# yamaHACK.net
KiCad netlist of a schematic drawn in EAGLE
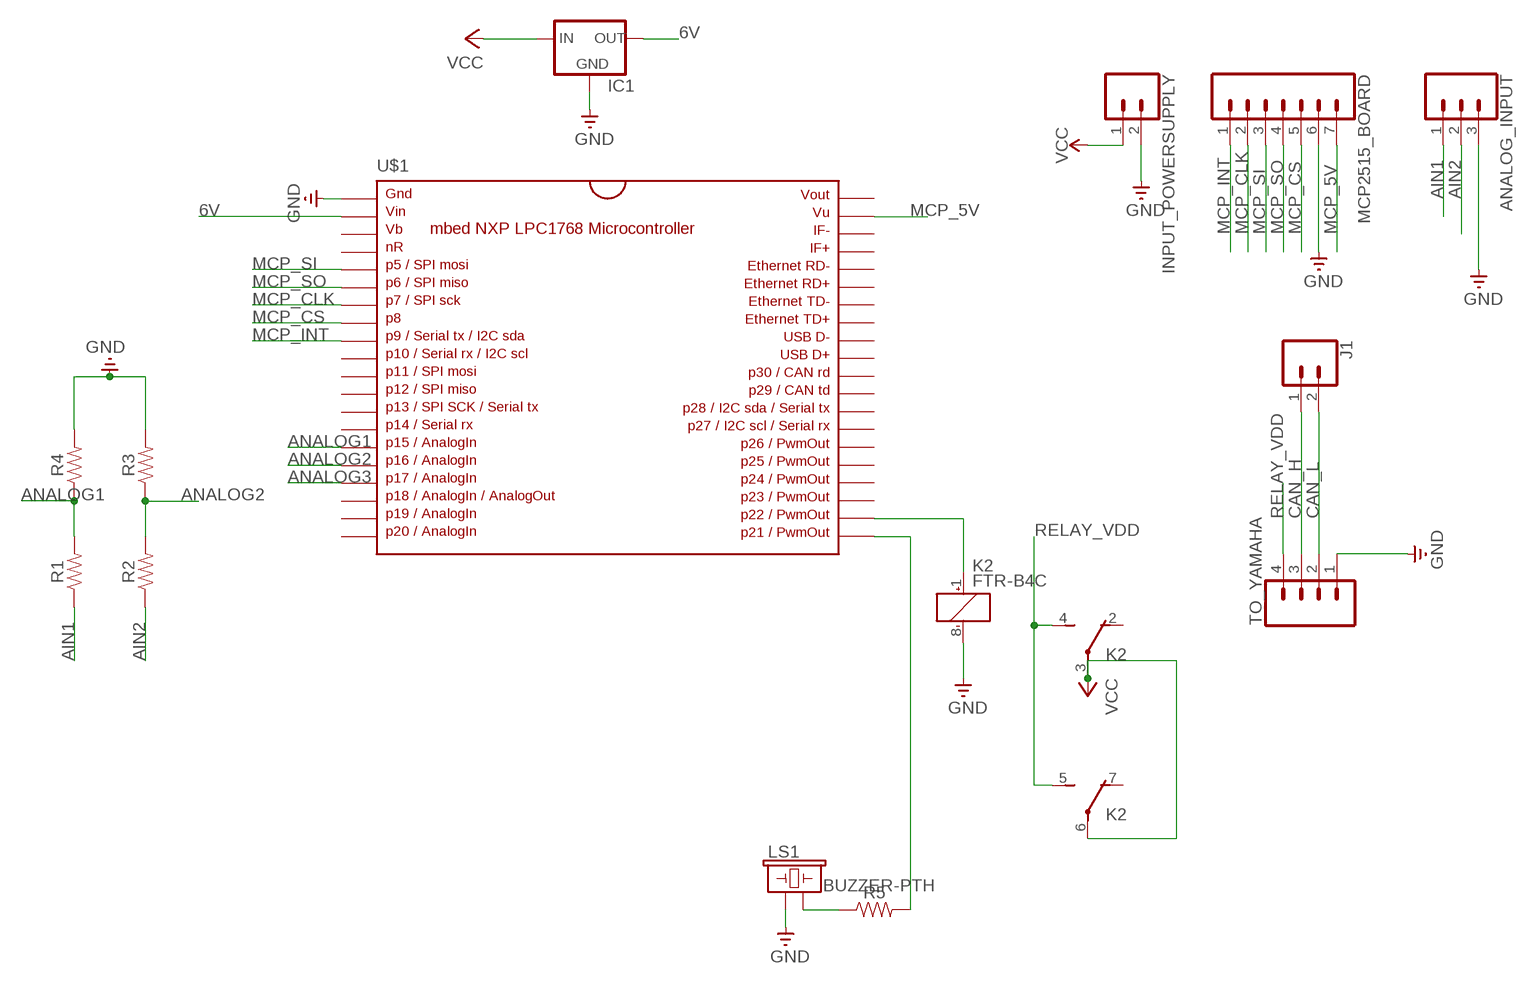
[diagram p0: schematic, sheet 1]

(export (version "E")
  (design (tool "Eeschema 10.0.6"))
  (components
    (comp (ref "ANALOG_INPUT")
      (value "CONN_03LONGPADS")
      (footprint "eagle-import:1X03_LONGPADS")
      (libsource (lib "eagle-import") (part "CONN_03LONGPADS"))
    )
    (comp (ref "IC1")
      (value "78MXXS")
      (footprint "eagle-import:78MXXS")
      (libsource (lib "eagle-import") (part "78MXXS"))
    )
    (comp (ref "INPUT_POWERSUPPLY")
      (value "CONN_02PTH3")
      (footprint "eagle-import:1X02_LONGPADS")
      (libsource (lib "eagle-import") (part "CONN_02PTH3"))
    )
    (comp (ref "J1")
      (value "CONN_02")
      (footprint "eagle-import:1X02")
      (libsource (lib "eagle-import") (part "CONN_02"))
    )
    (comp (ref "K2")
      (value "FTR-B4C")
      (footprint "eagle-import:FTR-B4C")
      (libsource (lib "eagle-import") (part "FTR-B4C"))
    )
    (comp (ref "LS1")
      (value "BUZZER-PTH")
      (footprint "eagle-import:BUZZER-12MM")
      (libsource (lib "eagle-import") (part "BUZZER-PTH"))
    )
    (comp (ref "MCP2515_BOARD")
      (value "CONN_07LONGPADS")
      (footprint "eagle-import:1X07_LONGPADS")
      (libsource (lib "eagle-import") (part "CONN_07LONGPADS"))
    )
    (comp (ref "R1")
      (value "RESISTORAXIAL-0.3")
      (footprint "eagle-import:AXIAL-0.3")
      (libsource (lib "eagle-import") (part "RESISTORAXIAL-0.3"))
    )
    (comp (ref "R2")
      (value "RESISTORAXIAL-0.3")
      (footprint "eagle-import:AXIAL-0.3")
      (libsource (lib "eagle-import") (part "RESISTORAXIAL-0.3"))
    )
    (comp (ref "R3")
      (value "RESISTORAXIAL-0.3")
      (footprint "eagle-import:AXIAL-0.3")
      (libsource (lib "eagle-import") (part "RESISTORAXIAL-0.3"))
    )
    (comp (ref "R4")
      (value "RESISTORAXIAL-0.3")
      (footprint "eagle-import:AXIAL-0.3")
      (libsource (lib "eagle-import") (part "RESISTORAXIAL-0.3"))
    )
    (comp (ref "R5")
      (value "RESISTORAXIAL-0.3")
      (footprint "eagle-import:AXIAL-0.3")
      (libsource (lib "eagle-import") (part "RESISTORAXIAL-0.3"))
    )
    (comp (ref "TO_YAMAHA")
      (value "CONN_04")
      (footprint "eagle-import:1X04")
      (libsource (lib "eagle-import") (part "CONN_04"))
    )
    (comp (ref "U$1")
      (value "MBED1768")
      (footprint "eagle-import:DIL40_0.9")
      (libsource (lib "eagle-import") (part "MBED_NXP_LPC1768"))
    )
  )
  (nets
    (net (code "1") (name "/6V") (class "Default")
      (node (ref "IC1") (pin "OUT") (pinfunction "OUT_OUT") (pintype "passive"))
      (node (ref "U$1") (pin "2") (pinfunction "P$2_2") (pintype "bidirectional"))
    )
    (net (code "2") (name "/AIN1") (class "Default")
      (node (ref "ANALOG_INPUT") (pin "1") (pinfunction "1_1") (pintype "passive"))
      (node (ref "R1") (pin "P$1") (pinfunction "1_P$1") (pintype "passive"))
    )
    (net (code "3") (name "/AIN2") (class "Default")
      (node (ref "ANALOG_INPUT") (pin "2") (pinfunction "2_2") (pintype "passive"))
      (node (ref "R2") (pin "P$1") (pinfunction "1_P$1") (pintype "passive"))
    )
    (net (code "4") (name "/ANALOG1") (class "Default")
      (node (ref "R1") (pin "P$2") (pinfunction "2_P$2") (pintype "passive"))
      (node (ref "R4") (pin "P$1") (pinfunction "1_P$1") (pintype "passive"))
      (node (ref "U$1") (pin "15") (pinfunction "P$15_15") (pintype "bidirectional"))
    )
    (net (code "5") (name "/ANALOG2") (class "Default")
      (node (ref "R2") (pin "P$2") (pinfunction "2_P$2") (pintype "passive"))
      (node (ref "R3") (pin "P$1") (pinfunction "1_P$1") (pintype "passive"))
      (node (ref "U$1") (pin "16") (pinfunction "P$16_16") (pintype "bidirectional"))
    )
    (net (code "6") (name "/ANALOG3") (class "Default")
      (node (ref "U$1") (pin "17") (pinfunction "P$17_17") (pintype "bidirectional"))
    )
    (net (code "7") (name "/CAN_H") (class "Default")
      (node (ref "J1") (pin "1") (pinfunction "1_1") (pintype "passive"))
      (node (ref "TO_YAMAHA") (pin "3") (pinfunction "3_3") (pintype "passive"))
    )
    (net (code "8") (name "/CAN_L") (class "Default")
      (node (ref "J1") (pin "2") (pinfunction "2_2") (pintype "passive"))
      (node (ref "TO_YAMAHA") (pin "2") (pinfunction "2_2") (pintype "passive"))
    )
    (net (code "9") (name "/MCP_5V") (class "Default")
      (node (ref "MCP2515_BOARD") (pin "7") (pinfunction "7_7") (pintype "passive"))
      (node (ref "U$1") (pin "39") (pinfunction "P$39_39") (pintype "bidirectional"))
    )
    (net (code "10") (name "/MCP_CLK") (class "Default")
      (node (ref "MCP2515_BOARD") (pin "2") (pinfunction "2_2") (pintype "passive"))
      (node (ref "U$1") (pin "7") (pinfunction "P$7_7") (pintype "bidirectional"))
    )
    (net (code "11") (name "/MCP_CS") (class "Default")
      (node (ref "MCP2515_BOARD") (pin "5") (pinfunction "5_5") (pintype "passive"))
      (node (ref "U$1") (pin "8") (pinfunction "P$8_8") (pintype "bidirectional"))
    )
    (net (code "12") (name "/MCP_INT") (class "Default")
      (node (ref "MCP2515_BOARD") (pin "1") (pinfunction "1_1") (pintype "passive"))
      (node (ref "U$1") (pin "9") (pinfunction "P$9_9") (pintype "bidirectional"))
    )
    (net (code "13") (name "/MCP_SI") (class "Default")
      (node (ref "MCP2515_BOARD") (pin "3") (pinfunction "3_3") (pintype "passive"))
      (node (ref "U$1") (pin "5") (pinfunction "P$5_5") (pintype "bidirectional"))
    )
    (net (code "14") (name "/MCP_SO") (class "Default")
      (node (ref "MCP2515_BOARD") (pin "4") (pinfunction "4_4") (pintype "passive"))
      (node (ref "U$1") (pin "6") (pinfunction "P$6_6") (pintype "bidirectional"))
    )
    (net (code "15") (name "/RELAY_VDD") (class "Default")
      (node (ref "K2") (pin "4") (pinfunction "S_4") (pintype "passive"))
      (node (ref "K2") (pin "5") (pinfunction "S_5") (pintype "passive"))
      (node (ref "TO_YAMAHA") (pin "4") (pinfunction "4_4") (pintype "passive"))
    )
    (net (code "16") (name "GND") (class "Default")
      (node (ref "ANALOG_INPUT") (pin "3") (pinfunction "3_3") (pintype "passive"))
      (node (ref "IC1") (pin "GND") (pinfunction "GND_GND") (pintype "input"))
      (node (ref "INPUT_POWERSUPPLY") (pin "2") (pinfunction "2_2") (pintype "passive"))
      (node (ref "K2") (pin "8") (pinfunction "-_8") (pintype "passive"))
      (node (ref "LS1") (pin "+") (pinfunction "1_+") (pintype "passive"))
      (node (ref "MCP2515_BOARD") (pin "6") (pinfunction "6_6") (pintype "passive"))
      (node (ref "R3") (pin "P$2") (pinfunction "2_P$2") (pintype "passive"))
      (node (ref "R4") (pin "P$2") (pinfunction "2_P$2") (pintype "passive"))
      (node (ref "TO_YAMAHA") (pin "1") (pinfunction "1_1") (pintype "passive"))
      (node (ref "U$1") (pin "1") (pinfunction "P$1_1") (pintype "bidirectional"))
    )
    (net (code "17") (name "Net-(K2C-+)") (class "Default")
      (node (ref "K2") (pin "1") (pinfunction "+_1") (pintype "passive"))
      (node (ref "U$1") (pin "22") (pinfunction "P$22_22") (pintype "bidirectional"))
    )
    (net (code "18") (name "Net-(LS1-2)") (class "Default")
      (node (ref "LS1") (pin "-") (pinfunction "2_-") (pintype "passive"))
      (node (ref "R5") (pin "P$1") (pinfunction "1_P$1") (pintype "passive"))
    )
    (net (code "19") (name "Net-(R5-2)") (class "Default")
      (node (ref "R5") (pin "P$2") (pinfunction "2_P$2") (pintype "passive"))
      (node (ref "U$1") (pin "21") (pinfunction "P$21_21") (pintype "bidirectional"))
    )
    (net (code "20") (name "VCC") (class "Default")
      (node (ref "IC1") (pin "IN") (pinfunction "IN_IN") (pintype "input"))
      (node (ref "INPUT_POWERSUPPLY") (pin "1") (pinfunction "1_1") (pintype "passive"))
      (node (ref "K2") (pin "3") (pinfunction "P_3") (pintype "passive"))
      (node (ref "K2") (pin "6") (pinfunction "P_6") (pintype "passive"))
    )
    (net (code "21") (name "unconnected-(K2A-O-Pad2)") (class "Default")
      (node (ref "K2") (pin "2") (pinfunction "O_2") (pintype "passive"))
    )
    (net (code "22") (name "unconnected-(K2B-O-Pad7)") (class "Default")
      (node (ref "K2") (pin "7") (pinfunction "O_7") (pintype "passive"))
    )
    (net (code "23") (name "unconnected-(U$1-P$3-Pad3)") (class "Default")
      (node (ref "U$1") (pin "3") (pinfunction "P$3_3") (pintype "bidirectional"))
    )
    (net (code "24") (name "unconnected-(U$1-P$4-Pad4)") (class "Default")
      (node (ref "U$1") (pin "4") (pinfunction "P$4_4") (pintype "bidirectional"))
    )
    (net (code "25") (name "unconnected-(U$1-P$10-Pad10)") (class "Default")
      (node (ref "U$1") (pin "10") (pinfunction "P$10_10") (pintype "bidirectional"))
    )
    (net (code "26") (name "unconnected-(U$1-P$11-Pad11)") (class "Default")
      (node (ref "U$1") (pin "11") (pinfunction "P$11_11") (pintype "bidirectional"))
    )
    (net (code "27") (name "unconnected-(U$1-P$12-Pad12)") (class "Default")
      (node (ref "U$1") (pin "12") (pinfunction "P$12_12") (pintype "bidirectional"))
    )
    (net (code "28") (name "unconnected-(U$1-P$13-Pad13)") (class "Default")
      (node (ref "U$1") (pin "13") (pinfunction "P$13_13") (pintype "bidirectional"))
    )
    (net (code "29") (name "unconnected-(U$1-P$14-Pad14)") (class "Default")
      (node (ref "U$1") (pin "14") (pinfunction "P$14_14") (pintype "bidirectional"))
    )
    (net (code "30") (name "unconnected-(U$1-P$18-Pad18)") (class "Default")
      (node (ref "U$1") (pin "18") (pinfunction "P$18_18") (pintype "bidirectional"))
    )
    (net (code "31") (name "unconnected-(U$1-P$19-Pad19)") (class "Default")
      (node (ref "U$1") (pin "19") (pinfunction "P$19_19") (pintype "bidirectional"))
    )
    (net (code "32") (name "unconnected-(U$1-P$20-Pad20)") (class "Default")
      (node (ref "U$1") (pin "20") (pinfunction "P$20_20") (pintype "bidirectional"))
    )
    (net (code "33") (name "unconnected-(U$1-P$23-Pad23)") (class "Default")
      (node (ref "U$1") (pin "23") (pinfunction "P$23_23") (pintype "bidirectional"))
    )
    (net (code "34") (name "unconnected-(U$1-P$24-Pad24)") (class "Default")
      (node (ref "U$1") (pin "24") (pinfunction "P$24_24") (pintype "bidirectional"))
    )
    (net (code "35") (name "unconnected-(U$1-P$25-Pad25)") (class "Default")
      (node (ref "U$1") (pin "25") (pinfunction "P$25_25") (pintype "bidirectional"))
    )
    (net (code "36") (name "unconnected-(U$1-P$26-Pad26)") (class "Default")
      (node (ref "U$1") (pin "26") (pinfunction "P$26_26") (pintype "bidirectional"))
    )
    (net (code "37") (name "unconnected-(U$1-P$27-Pad27)") (class "Default")
      (node (ref "U$1") (pin "27") (pinfunction "P$27_27") (pintype "bidirectional"))
    )
    (net (code "38") (name "unconnected-(U$1-P$28-Pad28)") (class "Default")
      (node (ref "U$1") (pin "28") (pinfunction "P$28_28") (pintype "bidirectional"))
    )
    (net (code "39") (name "unconnected-(U$1-P$29-Pad29)") (class "Default")
      (node (ref "U$1") (pin "29") (pinfunction "P$29_29") (pintype "bidirectional"))
    )
    (net (code "40") (name "unconnected-(U$1-P$30-Pad30)") (class "Default")
      (node (ref "U$1") (pin "30") (pinfunction "P$30_30") (pintype "bidirectional"))
    )
    (net (code "41") (name "unconnected-(U$1-P$31-Pad31)") (class "Default")
      (node (ref "U$1") (pin "31") (pinfunction "P$31_31") (pintype "bidirectional"))
    )
    (net (code "42") (name "unconnected-(U$1-P$32-Pad32)") (class "Default")
      (node (ref "U$1") (pin "32") (pinfunction "P$32_32") (pintype "bidirectional"))
    )
    (net (code "43") (name "unconnected-(U$1-P$33-Pad33)") (class "Default")
      (node (ref "U$1") (pin "33") (pinfunction "P$33_33") (pintype "bidirectional"))
    )
    (net (code "44") (name "unconnected-(U$1-P$34-Pad34)") (class "Default")
      (node (ref "U$1") (pin "34") (pinfunction "P$34_34") (pintype "bidirectional"))
    )
    (net (code "45") (name "unconnected-(U$1-P$35-Pad35)") (class "Default")
      (node (ref "U$1") (pin "35") (pinfunction "P$35_35") (pintype "bidirectional"))
    )
    (net (code "46") (name "unconnected-(U$1-P$36-Pad36)") (class "Default")
      (node (ref "U$1") (pin "36") (pinfunction "P$36_36") (pintype "bidirectional"))
    )
    (net (code "47") (name "unconnected-(U$1-P$37-Pad37)") (class "Default")
      (node (ref "U$1") (pin "37") (pinfunction "P$37_37") (pintype "bidirectional"))
    )
    (net (code "48") (name "unconnected-(U$1-P$38-Pad38)") (class "Default")
      (node (ref "U$1") (pin "38") (pinfunction "P$38_38") (pintype "bidirectional"))
    )
    (net (code "49") (name "unconnected-(U$1-P$40-Pad40)") (class "Default")
      (node (ref "U$1") (pin "40") (pinfunction "P$40_40") (pintype "bidirectional"))
    )
  )
)
